# devBoard.net
KiCad netlist of a schematic drawn in EAGLE
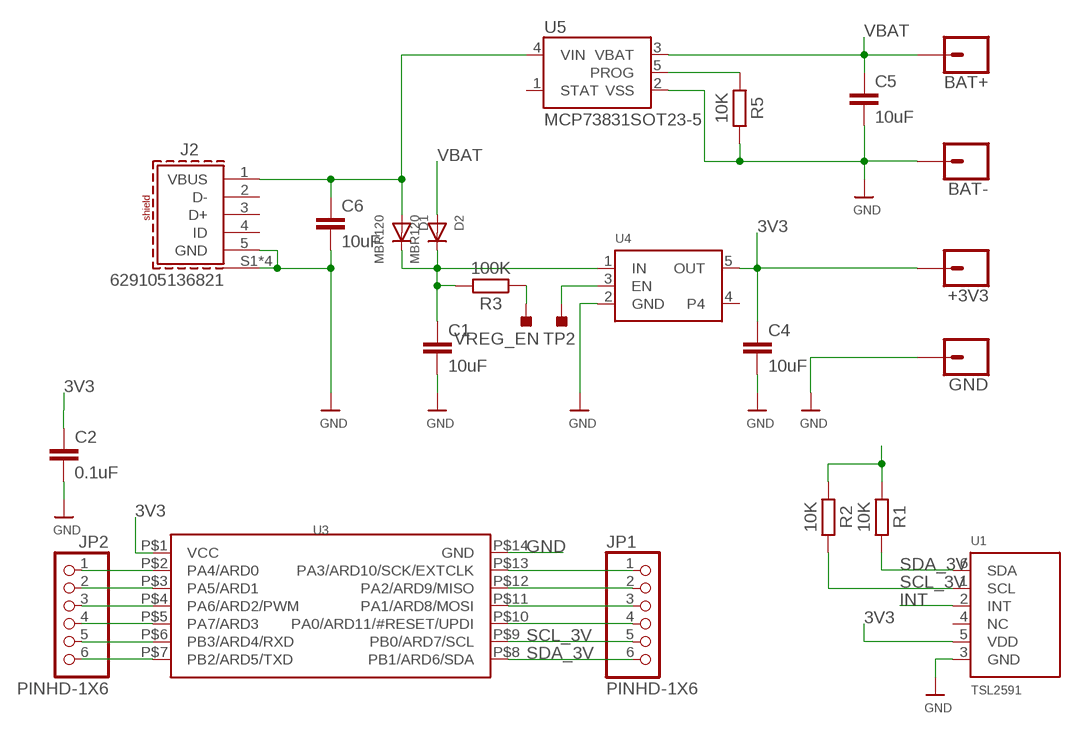
[diagram p0: schematic, sheet 1]

(export (version "E")
  (design (tool "Eeschema 10.0.6"))
  (components
    (comp (ref "+3V3")
      (value "CONN_01")
      (footprint "eagle-import:1X01")
      (libsource (lib "eagle-import") (part "CONN_01"))
    )
    (comp (ref "BAT+")
      (value "CONN_01")
      (footprint "eagle-import:1X01")
      (libsource (lib "eagle-import") (part "CONN_01"))
    )
    (comp (ref "BAT-")
      (value "CONN_01")
      (footprint "eagle-import:1X01")
      (libsource (lib "eagle-import") (part "CONN_01"))
    )
    (comp (ref "C1")
      (value "10uF")
      (footprint "eagle-import:0603")
      (libsource (lib "eagle-import") (part "10UF-0603-6.3V-20%"))
    )
    (comp (ref "C2")
      (value "0.1uF")
      (footprint "eagle-import:0603")
      (libsource (lib "eagle-import") (part "0.1UF-0603-25V-5%"))
    )
    (comp (ref "C4")
      (value "10uF")
      (footprint "eagle-import:0603")
      (libsource (lib "eagle-import") (part "10UF-0603-6.3V-20%"))
    )
    (comp (ref "C5")
      (value "10uF")
      (footprint "eagle-import:0603")
      (libsource (lib "eagle-import") (part "10UF-0603-6.3V-20%"))
    )
    (comp (ref "C6")
      (value "10uF")
      (footprint "eagle-import:0603")
      (libsource (lib "eagle-import") (part "10UF-0603-6.3V-20%"))
    )
    (comp (ref "D1")
      (value "MBR120")
      (footprint "eagle-import:SOD-123")
      (libsource (lib "eagle-import") (part "DIODESOD-123"))
    )
    (comp (ref "D2")
      (value "MBR120")
      (footprint "eagle-import:SOD-123")
      (libsource (lib "eagle-import") (part "DIODESOD-123"))
    )
    (comp (ref "GND")
      (value "CONN_01")
      (footprint "eagle-import:1X01")
      (libsource (lib "eagle-import") (part "CONN_01"))
    )
    (comp (ref "J2")
      (value "629105136821")
      (footprint "eagle-import:629105136821")
      (libsource (lib "eagle-import") (part "629105136821"))
    )
    (comp (ref "JP1")
      (value "PINHD-1X6")
      (footprint "eagle-import:1X06")
      (libsource (lib "eagle-import") (part "PINHD-1X6"))
    )
    (comp (ref "JP2")
      (value "PINHD-1X6")
      (footprint "eagle-import:1X06")
      (libsource (lib "eagle-import") (part "PINHD-1X6"))
    )
    (comp (ref "R1")
      (value "10K")
      (footprint "eagle-import:RESC1608X60")
      (libsource (lib "eagle-import") (part "RCHIP-0603(1608-METRIC)_"))
    )
    (comp (ref "R2")
      (value "10K")
      (footprint "eagle-import:RESC1608X60")
      (libsource (lib "eagle-import") (part "RCHIP-0603(1608-METRIC)_"))
    )
    (comp (ref "R3")
      (value "100K")
      (footprint "eagle-import:RESC1608X60")
      (libsource (lib "eagle-import") (part "RCHIP-0603(1608-METRIC)_"))
    )
    (comp (ref "R5")
      (value "10K")
      (footprint "eagle-import:RESC1608X60")
      (libsource (lib "eagle-import") (part "RCHIP-0603(1608-METRIC)_"))
    )
    (comp (ref "TP2")
      (value "TESTPOINT_TPS-PAD-036")
      (footprint "eagle-import:TESTPOINT_PAD-036")
      (libsource (lib "eagle-import") (part "TESTPOINT_TPS-PAD-036"))
    )
    (comp (ref "U1")
      (value "TSL2591")
      (footprint "eagle-import:DFN6_TAOS")
      (libsource (lib "eagle-import") (part "LIGHT_TSL2591"))
    )
    (comp (ref "U3")
      (value "ATTINY1604")
      (footprint "eagle-import:SOIC150")
      (libsource (lib "eagle-import") (part "ATTINY1604"))
    )
    (comp (ref "U4")
      (value "VREG_SOT23-5")
      (footprint "eagle-import:SOT23-5_1")
      (libsource (lib "eagle-import") (part "VREG_SOT23-5"))
    )
    (comp (ref "U5")
      (value "MCP73831SOT23-5")
      (footprint "eagle-import:SOT95P280X110-5")
      (libsource (lib "eagle-import") (part "MCP73831SOT23-5"))
    )
    (comp (ref "VREG_EN")
      (value "TESTPOINT_TPS-PAD-036")
      (footprint "eagle-import:TESTPOINT_PAD-036")
      (libsource (lib "eagle-import") (part "TESTPOINT_TPS-PAD-036"))
    )
  )
  (nets
    (net (code "1") (name "/3V3") (class "Default")
      (node (ref "+3V3") (pin "1") (pinfunction "1_1") (pintype "passive"))
      (node (ref "C2") (pin "1") (pinfunction "1_1") (pintype "passive"))
      (node (ref "C4") (pin "1") (pinfunction "1_1") (pintype "passive"))
      (node (ref "R1") (pin "1") (pinfunction "1_1") (pintype "passive"))
      (node (ref "R2") (pin "1") (pinfunction "1_1") (pintype "passive"))
      (node (ref "U1") (pin "5") (pinfunction "VDD_5") (pintype "power_in"))
      (node (ref "U3") (pin "P$1") (pinfunction "VCC_P$1") (pintype "power_in"))
      (node (ref "U4") (pin "5") (pinfunction "OUT_5") (pintype "power_in"))
    )
    (net (code "2") (name "/INT") (class "Default")
      (node (ref "U1") (pin "2") (pinfunction "INT_2") (pintype "output"))
    )
    (net (code "3") (name "/SCL_3V") (class "Default")
      (node (ref "JP1") (pin "5") (pinfunction "5_5") (pintype "passive"))
      (node (ref "R2") (pin "2") (pinfunction "2_2") (pintype "passive"))
      (node (ref "U1") (pin "1") (pinfunction "SCL_1") (pintype "bidirectional"))
      (node (ref "U3") (pin "P$9") (pinfunction "PB0/ARD7/SCL_P$9") (pintype "bidirectional"))
    )
    (net (code "4") (name "/SDA_3V") (class "Default")
      (node (ref "JP1") (pin "6") (pinfunction "6_6") (pintype "passive"))
      (node (ref "R1") (pin "2") (pinfunction "2_2") (pintype "passive"))
      (node (ref "U1") (pin "6") (pinfunction "SDA_6") (pintype "bidirectional"))
      (node (ref "U3") (pin "P$8") (pinfunction "PB1/ARD6/SDA_P$8") (pintype "bidirectional"))
    )
    (net (code "5") (name "/VBAT") (class "Default")
      (node (ref "BAT+") (pin "1") (pinfunction "1_1") (pintype "passive"))
      (node (ref "C5") (pin "1") (pinfunction "1_1") (pintype "passive"))
      (node (ref "D2") (pin "A") (pinfunction "A_A") (pintype "passive"))
      (node (ref "U5") (pin "3") (pinfunction "VBAT_3") (pintype "power_in"))
    )
    (net (code "6") (name "GND") (class "Default")
      (node (ref "BAT-") (pin "1") (pinfunction "1_1") (pintype "passive"))
      (node (ref "C1") (pin "2") (pinfunction "2_2") (pintype "passive"))
      (node (ref "C2") (pin "2") (pinfunction "2_2") (pintype "passive"))
      (node (ref "C4") (pin "2") (pinfunction "2_2") (pintype "passive"))
      (node (ref "C5") (pin "2") (pinfunction "2_2") (pintype "passive"))
      (node (ref "C6") (pin "2") (pinfunction "2_2") (pintype "passive"))
      (node (ref "GND") (pin "1") (pinfunction "1_1") (pintype "passive"))
      (node (ref "J2") (pin "5") (pinfunction "GND_5") (pintype "passive"))
      (node (ref "J2") (pin "S1") (pinfunction "SHIELD_S1") (pintype "passive"))
      (node (ref "J2") (pin "S2") (pinfunction "SHIELD_S2") (pintype "passive"))
      (node (ref "J2") (pin "S3") (pinfunction "SHIELD_S3") (pintype "passive"))
      (node (ref "J2") (pin "S4") (pinfunction "SHIELD_S4") (pintype "passive"))
      (node (ref "R5") (pin "2") (pinfunction "2_2") (pintype "passive"))
      (node (ref "U1") (pin "3") (pinfunction "GND_3") (pintype "power_in"))
      (node (ref "U3") (pin "P$14") (pinfunction "GND_P$14") (pintype "bidirectional"))
      (node (ref "U4") (pin "2") (pinfunction "GND_2") (pintype "power_in"))
      (node (ref "U5") (pin "2") (pinfunction "VSS_2") (pintype "power_in"))
    )
    (net (code "7") (name "Net-(J2-VBUS)") (class "Default")
      (node (ref "C6") (pin "1") (pinfunction "1_1") (pintype "passive"))
      (node (ref "D1") (pin "A") (pinfunction "A_A") (pintype "passive"))
      (node (ref "J2") (pin "1") (pinfunction "VBUS_1") (pintype "passive"))
      (node (ref "U5") (pin "4") (pinfunction "VIN_4") (pintype "power_in"))
    )
    (net (code "8") (name "Net-(TP2-TP)") (class "Default")
      (node (ref "TP2") (pin "1") (pinfunction "TP_1") (pintype "passive"))
      (node (ref "U4") (pin "3") (pinfunction "EN_3") (pintype "input"))
    )
    (net (code "9") (name "Net-(U3-PA0{slash}ARD11{slash}#RESET{slash}UPDI)") (class "Default")
      (node (ref "JP1") (pin "4") (pinfunction "4_4") (pintype "passive"))
      (node (ref "U3") (pin "P$10") (pinfunction "PA0/ARD11/#RESET/UPDI_P$10") (pintype "bidirectional"))
    )
    (net (code "10") (name "Net-(U3-PA1{slash}ARD8{slash}MOSI)") (class "Default")
      (node (ref "JP1") (pin "3") (pinfunction "3_3") (pintype "passive"))
      (node (ref "U3") (pin "P$11") (pinfunction "PA1/ARD8/MOSI_P$11") (pintype "bidirectional"))
    )
    (net (code "11") (name "Net-(U3-PA2{slash}ARD9{slash}MISO)") (class "Default")
      (node (ref "JP1") (pin "2") (pinfunction "2_2") (pintype "passive"))
      (node (ref "U3") (pin "P$12") (pinfunction "PA2/ARD9/MISO_P$12") (pintype "bidirectional"))
    )
    (net (code "12") (name "Net-(U3-PA3{slash}ARD10{slash}SCK{slash}EXTCLK)") (class "Default")
      (node (ref "JP1") (pin "1") (pinfunction "1_1") (pintype "passive"))
      (node (ref "U3") (pin "P$13") (pinfunction "PA3/ARD10/SCK/EXTCLK_P$13") (pintype "bidirectional"))
    )
    (net (code "13") (name "Net-(U3-PA4{slash}ARD0)") (class "Default")
      (node (ref "JP2") (pin "1") (pinfunction "1_1") (pintype "passive"))
      (node (ref "U3") (pin "P$2") (pinfunction "PA4/ARD0_P$2") (pintype "bidirectional"))
    )
    (net (code "14") (name "Net-(U3-PA5{slash}ARD1)") (class "Default")
      (node (ref "JP2") (pin "2") (pinfunction "2_2") (pintype "passive"))
      (node (ref "U3") (pin "P$3") (pinfunction "PA5/ARD1_P$3") (pintype "bidirectional"))
    )
    (net (code "15") (name "Net-(U3-PA6{slash}ARD2{slash}PWM)") (class "Default")
      (node (ref "JP2") (pin "3") (pinfunction "3_3") (pintype "passive"))
      (node (ref "U3") (pin "P$4") (pinfunction "PA6/ARD2/PWM_P$4") (pintype "bidirectional"))
    )
    (net (code "16") (name "Net-(U3-PA7{slash}ARD3)") (class "Default")
      (node (ref "JP2") (pin "4") (pinfunction "4_4") (pintype "passive"))
      (node (ref "U3") (pin "P$5") (pinfunction "PA7/ARD3_P$5") (pintype "bidirectional"))
    )
    (net (code "17") (name "Net-(U3-PB2{slash}ARD5{slash}TXD)") (class "Default")
      (node (ref "JP2") (pin "6") (pinfunction "6_6") (pintype "passive"))
      (node (ref "U3") (pin "P$7") (pinfunction "PB2/ARD5/TXD_P$7") (pintype "bidirectional"))
    )
    (net (code "18") (name "Net-(U3-PB3{slash}ARD4{slash}RXD)") (class "Default")
      (node (ref "JP2") (pin "5") (pinfunction "5_5") (pintype "passive"))
      (node (ref "U3") (pin "P$6") (pinfunction "PB3/ARD4/RXD_P$6") (pintype "bidirectional"))
    )
    (net (code "19") (name "Net-(U4-IN)") (class "Default")
      (node (ref "C1") (pin "1") (pinfunction "1_1") (pintype "passive"))
      (node (ref "D1") (pin "C") (pinfunction "C_C") (pintype "passive"))
      (node (ref "D2") (pin "C") (pinfunction "C_C") (pintype "passive"))
      (node (ref "R3") (pin "2") (pinfunction "2_2") (pintype "passive"))
      (node (ref "U4") (pin "1") (pinfunction "IN_1") (pintype "power_in"))
    )
    (net (code "20") (name "Net-(U5-PROG)") (class "Default")
      (node (ref "R5") (pin "1") (pinfunction "1_1") (pintype "passive"))
      (node (ref "U5") (pin "5") (pinfunction "PROG_5") (pintype "input"))
    )
    (net (code "21") (name "Net-(VREG_EN-TP)") (class "Default")
      (node (ref "R3") (pin "1") (pinfunction "1_1") (pintype "passive"))
      (node (ref "VREG_EN") (pin "1") (pinfunction "TP_1") (pintype "passive"))
    )
    (net (code "22") (name "unconnected-(J2-D+-Pad3)") (class "Default")
      (node (ref "J2") (pin "3") (pinfunction "D+_3") (pintype "passive"))
    )
    (net (code "23") (name "unconnected-(J2-D--Pad2)") (class "Default")
      (node (ref "J2") (pin "2") (pinfunction "D-_2") (pintype "passive"))
    )
    (net (code "24") (name "unconnected-(J2-ID-Pad4)") (class "Default")
      (node (ref "J2") (pin "4") (pinfunction "ID_4") (pintype "passive"))
    )
    (net (code "25") (name "unconnected-(U1-NC-Pad4)") (class "Default")
      (node (ref "U1") (pin "4") (pinfunction "NC_4") (pintype "no_connect"))
    )
    (net (code "26") (name "unconnected-(U4-P4-Pad4)") (class "Default")
      (node (ref "U4") (pin "4") (pinfunction "P4_4") (pintype "bidirectional"))
    )
    (net (code "27") (name "unconnected-(U5-STAT-Pad1)") (class "Default")
      (node (ref "U5") (pin "1") (pinfunction "STAT_1") (pintype "output"))
    )
  )
)
